# Alignment_driver.net
KiCad netlist of a schematic drawn in Altium Designer
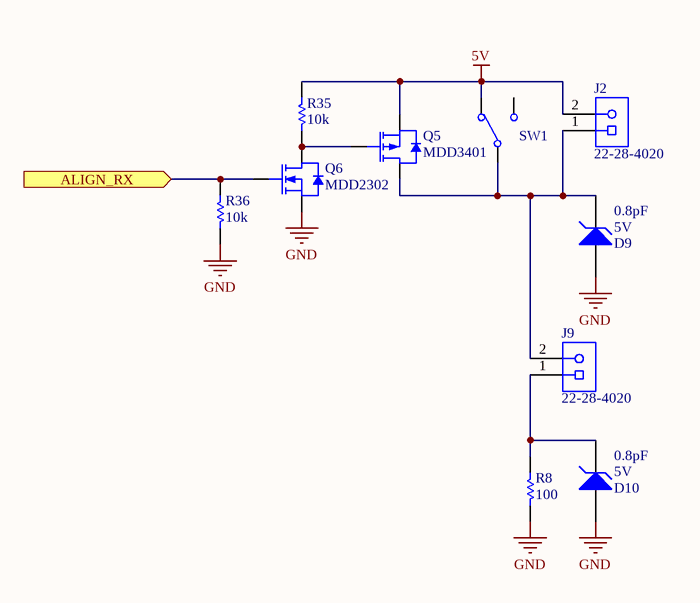
[diagram p0: Alignment_driver.SchDoc]

(export (version "E")
  (design (tool "Eeschema 10.0.6"))
  (components
    (comp (ref "D9")
      (value "5V")
      (footprint "DFN60P100X45-2L")
      (description "5A 55W 16V 9V Unidirectional 5V DFN1006-2L  ESD and Surge Protection (TVS/ESD) ROHS")
      (fields (field (name "CAPACITANCE") "0.8pF") (field (name "Comment") "H5VU10U"))
      (libsource (lib "UWA Aerospace") (part "Diode - Zener"))
    )
    (comp (ref "D10")
      (value "5V")
      (footprint "DFN60P100X45-2L")
      (description "5A 55W 16V 9V Unidirectional 5V DFN1006-2L  ESD and Surge Protection (TVS/ESD) ROHS")
      (fields (field (name "CAPACITANCE") "0.8pF") (field (name "Comment") "H5VU10U"))
      (libsource (lib "UWA Aerospace") (part "Diode - Zener"))
    )
    (comp (ref "J2")
      (value "22-28-4020")
      (footprint "22-28-4020-Footprint-1")
      (description "KK 254 Breakaway Header, Vertical, 2 Circuits, Tin (Sn) Plating, Mating Pin Length 6.09mm 2 POS")
      (fields (field (name "SOURCE") "Aliexpress"))
      (libsource (lib "UWA Aerospace") (part "22-28-4020"))
    )
    (comp (ref "J9")
      (value "22-28-4020")
      (footprint "22-28-4020-Footprint-1")
      (description "KK 254 Breakaway Header, Vertical, 2 Circuits, Tin (Sn) Plating, Mating Pin Length 6.09mm 2 POS")
      (fields (field (name "SOURCE") "Aliexpress"))
      (libsource (lib "UWA Aerospace") (part "22-28-4020"))
    )
    (comp (ref "Q5")
      (value "MDD3401")
      (footprint "SOT95P252X140-3N")
      (description "30V 4.2A 45mΩ@10V P Channel SOT-23 MOSFETs ROHS")
      (fields (field (name "SOURCE") "JLCPCB(Extended,Economic_PCBA)"))
      (libsource (lib "UWA Aerospace") (part "Transistor - MOSFET P-Channel"))
    )
    (comp (ref "Q6")
      (value "MDD2302")
      (footprint "SOT95P252X140-3N")
      (description "4A 25mΩ@4.5V null SOT-23 MOSFETs ROHS N CHANNEL")
      (libsource (lib "UWA Aerospace") (part "Transistor - MOSFET N-Channel"))
    )
    (comp (ref "R8")
      (value "100")
      (footprint "RESC1005X04N")
      (fields (field (name "TOLERANCE") "1%") (field (name "Comment") "0402WGF1000TCE"))
      (libsource (lib "UWA Aerospace") (part "Resistor"))
    )
    (comp (ref "R35")
      (value "10k")
      (footprint "RESC1005X04N")
      (description "Res Thick Film 0402 10K Ohm 1% 1/16W ±100ppm/°C Molded SMD Paper T/R")
      (fields (field (name "TOLERANCE") "1%") (field (name "Comment") "CRCW0402-10K0FKED"))
      (libsource (lib "UWA Aerospace") (part "Resistor"))
    )
    (comp (ref "R36")
      (value "10k")
      (footprint "RESC1005X04N")
      (description "Res Thick Film 0402 10K Ohm 1% 1/16W ±100ppm/°C Molded SMD Paper T/R")
      (fields (field (name "TOLERANCE") "1%") (field (name "Comment") "CRCW0402-10K0FKED"))
      (libsource (lib "UWA Aerospace") (part "Resistor"))
    )
    (comp (ref "SW1")
      (value "PCM12SMTR")
      (footprint "PCM12SMTR-Footprint-1")
      (description "C & K COMPONENTS - PCM12SMTR - SWITCH, SPDT, 0.3A, 6VDC, SMD")
      (fields (field (name "SOURCE") "Distributor"))
      (libsource (lib "UWA Aerospace") (part "1825232-1"))
    )
  )
  (nets
    (net (code "1") (name "/ALIGN_RX") (class "Default")
      (node (ref "Q6") (pin "1") (pinfunction "G_1") (pintype "passive"))
      (node (ref "R36") (pin "2") (pinfunction "2_2") (pintype "passive"))
    )
    (net (code "2") (name "5V") (class "Default")
      (node (ref "J2") (pin "2") (pinfunction "2_2") (pintype "passive"))
      (node (ref "Q5") (pin "2") (pinfunction "S_2") (pintype "passive"))
      (node (ref "R35") (pin "2") (pinfunction "2_2") (pintype "passive"))
      (node (ref "SW1") (pin "3") (pinfunction "3_3") (pintype "passive"))
    )
    (net (code "3") (name "GND") (class "Default")
      (node (ref "D10") (pin "2") (pinfunction "A_2") (pintype "passive"))
      (node (ref "D9") (pin "2") (pinfunction "A_2") (pintype "passive"))
      (node (ref "Q6") (pin "2") (pinfunction "S_2") (pintype "passive"))
      (node (ref "R36") (pin "1") (pinfunction "1_1") (pintype "passive"))
      (node (ref "R8") (pin "1") (pinfunction "1_1") (pintype "passive"))
    )
    (net (code "4") (name "Net-(D9-K)") (class "Default")
      (node (ref "D9") (pin "1") (pinfunction "K_1") (pintype "passive"))
      (node (ref "J2") (pin "1") (pinfunction "1_1") (pintype "passive"))
      (node (ref "J9") (pin "2") (pinfunction "2_2") (pintype "passive"))
      (node (ref "Q5") (pin "3") (pinfunction "D_3") (pintype "passive"))
      (node (ref "SW1") (pin "2") (pinfunction "2_2") (pintype "passive"))
    )
    (net (code "5") (name "Net-(D10-K)") (class "Default")
      (node (ref "D10") (pin "1") (pinfunction "K_1") (pintype "passive"))
      (node (ref "J9") (pin "1") (pinfunction "1_1") (pintype "passive"))
      (node (ref "R8") (pin "2") (pinfunction "2_2") (pintype "passive"))
    )
    (net (code "6") (name "Net-(Q5-G)") (class "Default")
      (node (ref "Q5") (pin "1") (pinfunction "G_1") (pintype "passive"))
      (node (ref "Q6") (pin "3") (pinfunction "D_3") (pintype "passive"))
      (node (ref "R35") (pin "1") (pinfunction "1_1") (pintype "passive"))
    )
    (net (code "7") (name "unconnected-(SW1-Pad1)") (class "Default")
      (node (ref "SW1") (pin "1") (pinfunction "1_1") (pintype "passive"))
    )
  )
)
